# pioneer_2-bluepill_eletronic_wrapper.net
KiCad netlist of a schematic drawn in Altium Designer
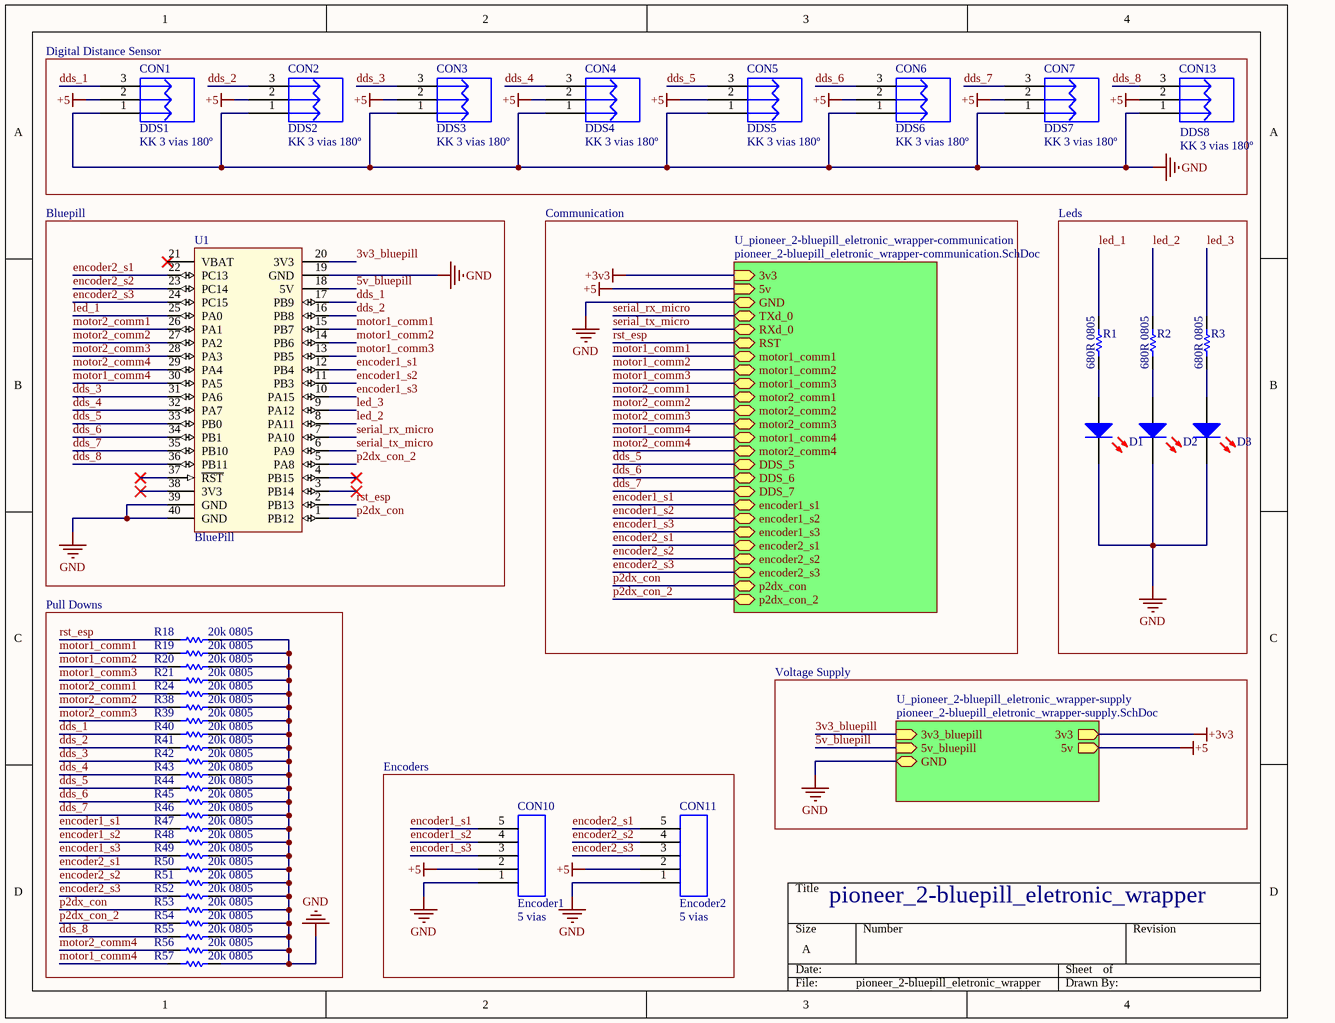
[diagram p0: pioneer_2-bluepill_eletronic_wrapper.SchDoc]

(export (version "E")
  (design (tool "Eeschema 10.0.6"))
  (components
    (comp (ref "CON1")
      (value "DDS1")
      (footprint "KK_3vias_180º")
      (description "Conector KK 2.54mm 3 vias")
      (fields (field (name "VALOR") "KK 3 vias 180º"))
      (libsource (lib "pioneer_2-bluepill_eletronic_wrapper") (part "KK_2.54_3vias"))
    )
    (comp (ref "CON2")
      (value "DDS2")
      (footprint "KK_3vias_180º")
      (description "Conector KK 2.54mm 3 vias")
      (fields (field (name "VALOR") "KK 3 vias 180º"))
      (libsource (lib "pioneer_2-bluepill_eletronic_wrapper") (part "KK_2.54_3vias"))
    )
    (comp (ref "CON3")
      (value "DDS3")
      (footprint "KK_3vias_180º")
      (description "Conector KK 2.54mm 3 vias")
      (fields (field (name "VALOR") "KK 3 vias 180º"))
      (libsource (lib "pioneer_2-bluepill_eletronic_wrapper") (part "KK_2.54_3vias"))
    )
    (comp (ref "CON4")
      (value "DDS4")
      (footprint "KK_3vias_180º")
      (description "Conector KK 2.54mm 3 vias")
      (fields (field (name "VALOR") "KK 3 vias 180º"))
      (libsource (lib "pioneer_2-bluepill_eletronic_wrapper") (part "KK_2.54_3vias"))
    )
    (comp (ref "CON5")
      (value "DDS5")
      (footprint "KK_3vias_180º")
      (description "Conector KK 2.54mm 3 vias")
      (fields (field (name "VALOR") "KK 3 vias 180º"))
      (libsource (lib "pioneer_2-bluepill_eletronic_wrapper") (part "KK_2.54_3vias"))
    )
    (comp (ref "CON6")
      (value "DDS6")
      (footprint "KK_3vias_180º")
      (description "Conector KK 2.54mm 3 vias")
      (fields (field (name "VALOR") "KK 3 vias 180º"))
      (libsource (lib "pioneer_2-bluepill_eletronic_wrapper") (part "KK_2.54_3vias"))
    )
    (comp (ref "CON7")
      (value "DDS7")
      (footprint "KK_3vias_180º")
      (description "Conector KK 2.54mm 3 vias")
      (fields (field (name "VALOR") "KK 3 vias 180º"))
      (libsource (lib "pioneer_2-bluepill_eletronic_wrapper") (part "KK_2.54_3vias"))
    )
    (comp (ref "CON10")
      (value "Encoder1")
      (footprint "5vias")
      (description "holes 2.54mm 5 vias")
      (fields (field (name "VALOR") "5 vias"))
      (libsource (lib "pioneer_2-bluepill_eletronic_wrapper") (part "2.54_5vias"))
    )
    (comp (ref "CON11")
      (value "Encoder2")
      (footprint "5vias")
      (description "holes 2.54mm 5 vias")
      (fields (field (name "VALOR") "5 vias"))
      (libsource (lib "pioneer_2-bluepill_eletronic_wrapper") (part "2.54_5vias"))
    )
    (comp (ref "CON13")
      (value "DDS8")
      (footprint "KK_3vias_180º")
      (description "Conector KK 2.54mm 3 vias")
      (fields (field (name "VALOR") "KK 3 vias 180º"))
      (libsource (lib "pioneer_2-bluepill_eletronic_wrapper") (part "KK_2.54_3vias"))
    )
    (comp (ref "D1")
      (value "LED 3MM RED")
      (footprint "LED RED")
      (fields (field (name "MANUFACTURER") "Paralight") (field (name "MANUFACTURER PART NUMBER") "IMP585"))
      (libsource (lib "pioneer_2-bluepill_eletronic_wrapper") (part "LED 3MM RED"))
    )
    (comp (ref "D2")
      (value "LED 3MM RED")
      (footprint "LED RED")
      (fields (field (name "MANUFACTURER") "Paralight") (field (name "MANUFACTURER PART NUMBER") "IMP585"))
      (libsource (lib "pioneer_2-bluepill_eletronic_wrapper") (part "LED 3MM RED"))
    )
    (comp (ref "D3")
      (value "LED 3MM RED")
      (footprint "LED RED")
      (fields (field (name "MANUFACTURER") "Paralight") (field (name "MANUFACTURER PART NUMBER") "IMP585"))
      (libsource (lib "pioneer_2-bluepill_eletronic_wrapper") (part "LED 3MM RED"))
    )
    (comp (ref "R1")
      (value "680R 0805")
      (footprint "RESISTOR 0805")
      (description "0805")
      (fields
        (field (name "MANUFACTURER") "PANASONIC ELECTRONIC COMPONENTS")
        (field (name "MANUFACTURER PART NUMBER") "ERJ-3GEY0R00V")
      )
      (libsource (lib "pioneer_2-bluepill_eletronic_wrapper") (part "RES 0805 5%"))
    )
    (comp (ref "R2")
      (value "680R 0805")
      (footprint "RESISTOR 0805")
      (description "0805")
      (fields
        (field (name "MANUFACTURER") "PANASONIC ELECTRONIC COMPONENTS")
        (field (name "MANUFACTURER PART NUMBER") "ERJ-3GEY0R00V")
      )
      (libsource (lib "pioneer_2-bluepill_eletronic_wrapper") (part "RES 0805 5%"))
    )
    (comp (ref "R3")
      (value "680R 0805")
      (footprint "RESISTOR 0805")
      (description "0805")
      (fields
        (field (name "MANUFACTURER") "PANASONIC ELECTRONIC COMPONENTS")
        (field (name "MANUFACTURER PART NUMBER") "ERJ-3GEY0R00V")
      )
      (libsource (lib "pioneer_2-bluepill_eletronic_wrapper") (part "RES 0805 5%"))
    )
    (comp (ref "R18")
      (value "20k 0805")
      (footprint "RESISTOR 0805")
      (description "0805")
      (fields
        (field (name "MANUFACTURER") "PANASONIC ELECTRONIC COMPONENTS")
        (field (name "MANUFACTURER PART NUMBER") "ERJ-3GEY0R00V")
      )
      (libsource (lib "pioneer_2-bluepill_eletronic_wrapper") (part "RES 0805 5%"))
    )
    (comp (ref "R19")
      (value "20k 0805")
      (footprint "RESISTOR 0805")
      (description "0805")
      (fields
        (field (name "MANUFACTURER") "PANASONIC ELECTRONIC COMPONENTS")
        (field (name "MANUFACTURER PART NUMBER") "ERJ-3GEY0R00V")
      )
      (libsource (lib "pioneer_2-bluepill_eletronic_wrapper") (part "RES 0805 5%"))
    )
    (comp (ref "R20")
      (value "20k 0805")
      (footprint "RESISTOR 0805")
      (description "0805")
      (fields
        (field (name "MANUFACTURER") "PANASONIC ELECTRONIC COMPONENTS")
        (field (name "MANUFACTURER PART NUMBER") "ERJ-3GEY0R00V")
      )
      (libsource (lib "pioneer_2-bluepill_eletronic_wrapper") (part "RES 0805 5%"))
    )
    (comp (ref "R21")
      (value "20k 0805")
      (footprint "RESISTOR 0805")
      (description "0805")
      (fields
        (field (name "MANUFACTURER") "PANASONIC ELECTRONIC COMPONENTS")
        (field (name "MANUFACTURER PART NUMBER") "ERJ-3GEY0R00V")
      )
      (libsource (lib "pioneer_2-bluepill_eletronic_wrapper") (part "RES 0805 5%"))
    )
    (comp (ref "R24")
      (value "20k 0805")
      (footprint "RESISTOR 0805")
      (description "0805")
      (fields
        (field (name "MANUFACTURER") "PANASONIC ELECTRONIC COMPONENTS")
        (field (name "MANUFACTURER PART NUMBER") "ERJ-3GEY0R00V")
      )
      (libsource (lib "pioneer_2-bluepill_eletronic_wrapper") (part "RES 0805 5%"))
    )
    (comp (ref "R38")
      (value "20k 0805")
      (footprint "RESISTOR 0805")
      (description "0805")
      (fields
        (field (name "MANUFACTURER") "PANASONIC ELECTRONIC COMPONENTS")
        (field (name "MANUFACTURER PART NUMBER") "ERJ-3GEY0R00V")
      )
      (libsource (lib "pioneer_2-bluepill_eletronic_wrapper") (part "RES 0805 5%"))
    )
    (comp (ref "R39")
      (value "20k 0805")
      (footprint "RESISTOR 0805")
      (description "0805")
      (fields
        (field (name "MANUFACTURER") "PANASONIC ELECTRONIC COMPONENTS")
        (field (name "MANUFACTURER PART NUMBER") "ERJ-3GEY0R00V")
      )
      (libsource (lib "pioneer_2-bluepill_eletronic_wrapper") (part "RES 0805 5%"))
    )
    (comp (ref "R40")
      (value "20k 0805")
      (footprint "RESISTOR 0805")
      (description "0805")
      (fields
        (field (name "MANUFACTURER") "PANASONIC ELECTRONIC COMPONENTS")
        (field (name "MANUFACTURER PART NUMBER") "ERJ-3GEY0R00V")
      )
      (libsource (lib "pioneer_2-bluepill_eletronic_wrapper") (part "RES 0805 5%"))
    )
    (comp (ref "R41")
      (value "20k 0805")
      (footprint "RESISTOR 0805")
      (description "0805")
      (fields
        (field (name "MANUFACTURER") "PANASONIC ELECTRONIC COMPONENTS")
        (field (name "MANUFACTURER PART NUMBER") "ERJ-3GEY0R00V")
      )
      (libsource (lib "pioneer_2-bluepill_eletronic_wrapper") (part "RES 0805 5%"))
    )
    (comp (ref "R42")
      (value "20k 0805")
      (footprint "RESISTOR 0805")
      (description "0805")
      (fields
        (field (name "MANUFACTURER") "PANASONIC ELECTRONIC COMPONENTS")
        (field (name "MANUFACTURER PART NUMBER") "ERJ-3GEY0R00V")
      )
      (libsource (lib "pioneer_2-bluepill_eletronic_wrapper") (part "RES 0805 5%"))
    )
    (comp (ref "R43")
      (value "20k 0805")
      (footprint "RESISTOR 0805")
      (description "0805")
      (fields
        (field (name "MANUFACTURER") "PANASONIC ELECTRONIC COMPONENTS")
        (field (name "MANUFACTURER PART NUMBER") "ERJ-3GEY0R00V")
      )
      (libsource (lib "pioneer_2-bluepill_eletronic_wrapper") (part "RES 0805 5%"))
    )
    (comp (ref "R44")
      (value "20k 0805")
      (footprint "RESISTOR 0805")
      (description "0805")
      (fields
        (field (name "MANUFACTURER") "PANASONIC ELECTRONIC COMPONENTS")
        (field (name "MANUFACTURER PART NUMBER") "ERJ-3GEY0R00V")
      )
      (libsource (lib "pioneer_2-bluepill_eletronic_wrapper") (part "RES 0805 5%"))
    )
    (comp (ref "R45")
      (value "20k 0805")
      (footprint "RESISTOR 0805")
      (description "0805")
      (fields
        (field (name "MANUFACTURER") "PANASONIC ELECTRONIC COMPONENTS")
        (field (name "MANUFACTURER PART NUMBER") "ERJ-3GEY0R00V")
      )
      (libsource (lib "pioneer_2-bluepill_eletronic_wrapper") (part "RES 0805 5%"))
    )
    (comp (ref "R46")
      (value "20k 0805")
      (footprint "RESISTOR 0805")
      (description "0805")
      (fields
        (field (name "MANUFACTURER") "PANASONIC ELECTRONIC COMPONENTS")
        (field (name "MANUFACTURER PART NUMBER") "ERJ-3GEY0R00V")
      )
      (libsource (lib "pioneer_2-bluepill_eletronic_wrapper") (part "RES 0805 5%"))
    )
    (comp (ref "R47")
      (value "20k 0805")
      (footprint "RESISTOR 0805")
      (description "0805")
      (fields
        (field (name "MANUFACTURER") "PANASONIC ELECTRONIC COMPONENTS")
        (field (name "MANUFACTURER PART NUMBER") "ERJ-3GEY0R00V")
      )
      (libsource (lib "pioneer_2-bluepill_eletronic_wrapper") (part "RES 0805 5%"))
    )
    (comp (ref "R48")
      (value "20k 0805")
      (footprint "RESISTOR 0805")
      (description "0805")
      (fields
        (field (name "MANUFACTURER") "PANASONIC ELECTRONIC COMPONENTS")
        (field (name "MANUFACTURER PART NUMBER") "ERJ-3GEY0R00V")
      )
      (libsource (lib "pioneer_2-bluepill_eletronic_wrapper") (part "RES 0805 5%"))
    )
    (comp (ref "R49")
      (value "20k 0805")
      (footprint "RESISTOR 0805")
      (description "0805")
      (fields
        (field (name "MANUFACTURER") "PANASONIC ELECTRONIC COMPONENTS")
        (field (name "MANUFACTURER PART NUMBER") "ERJ-3GEY0R00V")
      )
      (libsource (lib "pioneer_2-bluepill_eletronic_wrapper") (part "RES 0805 5%"))
    )
    (comp (ref "R50")
      (value "20k 0805")
      (footprint "RESISTOR 0805")
      (description "0805")
      (fields
        (field (name "MANUFACTURER") "PANASONIC ELECTRONIC COMPONENTS")
        (field (name "MANUFACTURER PART NUMBER") "ERJ-3GEY0R00V")
      )
      (libsource (lib "pioneer_2-bluepill_eletronic_wrapper") (part "RES 0805 5%"))
    )
    (comp (ref "R51")
      (value "20k 0805")
      (footprint "RESISTOR 0805")
      (description "0805")
      (fields
        (field (name "MANUFACTURER") "PANASONIC ELECTRONIC COMPONENTS")
        (field (name "MANUFACTURER PART NUMBER") "ERJ-3GEY0R00V")
      )
      (libsource (lib "pioneer_2-bluepill_eletronic_wrapper") (part "RES 0805 5%"))
    )
    (comp (ref "R52")
      (value "20k 0805")
      (footprint "RESISTOR 0805")
      (description "0805")
      (fields
        (field (name "MANUFACTURER") "PANASONIC ELECTRONIC COMPONENTS")
        (field (name "MANUFACTURER PART NUMBER") "ERJ-3GEY0R00V")
      )
      (libsource (lib "pioneer_2-bluepill_eletronic_wrapper") (part "RES 0805 5%"))
    )
    (comp (ref "R53")
      (value "20k 0805")
      (footprint "RESISTOR 0805")
      (description "0805")
      (fields
        (field (name "MANUFACTURER") "PANASONIC ELECTRONIC COMPONENTS")
        (field (name "MANUFACTURER PART NUMBER") "ERJ-3GEY0R00V")
      )
      (libsource (lib "pioneer_2-bluepill_eletronic_wrapper") (part "RES 0805 5%"))
    )
    (comp (ref "R54")
      (value "20k 0805")
      (footprint "RESISTOR 0805")
      (description "0805")
      (fields
        (field (name "MANUFACTURER") "PANASONIC ELECTRONIC COMPONENTS")
        (field (name "MANUFACTURER PART NUMBER") "ERJ-3GEY0R00V")
      )
      (libsource (lib "pioneer_2-bluepill_eletronic_wrapper") (part "RES 0805 5%"))
    )
    (comp (ref "R55")
      (value "20k 0805")
      (footprint "RESISTOR 0805")
      (description "0805")
      (fields
        (field (name "MANUFACTURER") "PANASONIC ELECTRONIC COMPONENTS")
        (field (name "MANUFACTURER PART NUMBER") "ERJ-3GEY0R00V")
      )
      (libsource (lib "pioneer_2-bluepill_eletronic_wrapper") (part "RES 0805 5%"))
    )
    (comp (ref "R56")
      (value "20k 0805")
      (footprint "RESISTOR 0805")
      (description "0805")
      (fields
        (field (name "MANUFACTURER") "PANASONIC ELECTRONIC COMPONENTS")
        (field (name "MANUFACTURER PART NUMBER") "ERJ-3GEY0R00V")
      )
      (libsource (lib "pioneer_2-bluepill_eletronic_wrapper") (part "RES 0805 5%"))
    )
    (comp (ref "R57")
      (value "20k 0805")
      (footprint "RESISTOR 0805")
      (description "0805")
      (fields
        (field (name "MANUFACTURER") "PANASONIC ELECTRONIC COMPONENTS")
        (field (name "MANUFACTURER PART NUMBER") "ERJ-3GEY0R00V")
      )
      (libsource (lib "pioneer_2-bluepill_eletronic_wrapper") (part "RES 0805 5%"))
    )
    (comp (ref "U1")
      (value "BluePill")
      (footprint "BluePill")
      (description "BluePill - STMDuino (STM32F103)")
      (fields (field (name "SOURCE") "uControlador.SchLib"))
      (libsource (lib "pioneer_2-bluepill_eletronic_wrapper") (part "CMP-010-000000-1"))
    )
  )
  (nets
    (net (code "2") (name "+5") (class "Default")
      (node (ref "CON1") (pin "2") (pintype "passive"))
      (node (ref "CON10") (pin "2") (pintype "passive"))
      (node (ref "CON11") (pin "2") (pintype "passive"))
      (node (ref "CON13") (pin "2") (pintype "passive"))
      (node (ref "CON2") (pin "2") (pintype "passive"))
      (node (ref "CON3") (pin "2") (pintype "passive"))
      (node (ref "CON4") (pin "2") (pintype "passive"))
      (node (ref "CON5") (pin "2") (pintype "passive"))
      (node (ref "CON6") (pin "2") (pintype "passive"))
      (node (ref "CON7") (pin "2") (pintype "passive"))
    )
    (net (code "3") (name "/3v3_bluepill") (class "Default")
      (node (ref "U1") (pin "20") (pinfunction "3V3_20") (pintype "passive"))
    )
    (net (code "4") (name "/5v_bluepill") (class "Default")
      (node (ref "U1") (pin "18") (pinfunction "5V_18") (pintype "power_in"))
    )
    (net (code "5") (name "/dds_1") (class "Default")
      (node (ref "CON1") (pin "3") (pintype "passive"))
      (node (ref "R40") (pin "1") (pinfunction "1_1") (pintype "passive"))
      (node (ref "U1") (pin "17") (pinfunction "PB9_17") (pintype "bidirectional"))
    )
    (net (code "6") (name "/dds_2") (class "Default")
      (node (ref "CON2") (pin "3") (pintype "passive"))
      (node (ref "R41") (pin "1") (pinfunction "1_1") (pintype "passive"))
      (node (ref "U1") (pin "16") (pinfunction "PB8_16") (pintype "bidirectional"))
    )
    (net (code "7") (name "/dds_3") (class "Default")
      (node (ref "CON3") (pin "3") (pintype "passive"))
      (node (ref "R42") (pin "1") (pinfunction "1_1") (pintype "passive"))
      (node (ref "U1") (pin "31") (pinfunction "PA6_31") (pintype "bidirectional"))
    )
    (net (code "8") (name "/dds_4") (class "Default")
      (node (ref "CON4") (pin "3") (pintype "passive"))
      (node (ref "R43") (pin "1") (pinfunction "1_1") (pintype "passive"))
      (node (ref "U1") (pin "32") (pinfunction "PA7_32") (pintype "bidirectional"))
    )
    (net (code "9") (name "/dds_5") (class "Default")
      (node (ref "CON5") (pin "3") (pintype "passive"))
      (node (ref "R44") (pin "1") (pinfunction "1_1") (pintype "passive"))
      (node (ref "U1") (pin "33") (pinfunction "PB0_33") (pintype "bidirectional"))
    )
    (net (code "10") (name "/dds_6") (class "Default")
      (node (ref "CON6") (pin "3") (pintype "passive"))
      (node (ref "R45") (pin "1") (pinfunction "1_1") (pintype "passive"))
      (node (ref "U1") (pin "34") (pinfunction "PB1_34") (pintype "bidirectional"))
    )
    (net (code "11") (name "/dds_7") (class "Default")
      (node (ref "CON7") (pin "3") (pintype "passive"))
      (node (ref "R46") (pin "1") (pinfunction "1_1") (pintype "passive"))
      (node (ref "U1") (pin "35") (pinfunction "PB10_35") (pintype "bidirectional"))
    )
    (net (code "12") (name "/dds_8") (class "Default")
      (node (ref "CON13") (pin "3") (pintype "passive"))
      (node (ref "R55") (pin "1") (pinfunction "1_1") (pintype "passive"))
      (node (ref "U1") (pin "36") (pinfunction "PB11_36") (pintype "bidirectional"))
    )
    (net (code "13") (name "/encoder1_s1") (class "Default")
      (node (ref "CON10") (pin "5") (pintype "passive"))
      (node (ref "R47") (pin "1") (pinfunction "1_1") (pintype "passive"))
      (node (ref "U1") (pin "12") (pinfunction "PB4_12") (pintype "bidirectional"))
    )
    (net (code "14") (name "/encoder1_s2") (class "Default")
      (node (ref "CON10") (pin "4") (pintype "passive"))
      (node (ref "R48") (pin "1") (pinfunction "1_1") (pintype "passive"))
      (node (ref "U1") (pin "11") (pinfunction "PB3_11") (pintype "bidirectional"))
    )
    (net (code "15") (name "/encoder1_s3") (class "Default")
      (node (ref "CON10") (pin "3") (pintype "passive"))
      (node (ref "R49") (pin "1") (pinfunction "1_1") (pintype "passive"))
      (node (ref "U1") (pin "10") (pinfunction "PA15_10") (pintype "bidirectional"))
    )
    (net (code "16") (name "/encoder2_s1") (class "Default")
      (node (ref "CON11") (pin "5") (pintype "passive"))
      (node (ref "R50") (pin "1") (pinfunction "1_1") (pintype "passive"))
      (node (ref "U1") (pin "22") (pinfunction "PC13_22") (pintype "bidirectional"))
    )
    (net (code "17") (name "/encoder2_s2") (class "Default")
      (node (ref "CON11") (pin "4") (pintype "passive"))
      (node (ref "R51") (pin "1") (pinfunction "1_1") (pintype "passive"))
      (node (ref "U1") (pin "23") (pinfunction "PC14_23") (pintype "bidirectional"))
    )
    (net (code "18") (name "/encoder2_s3") (class "Default")
      (node (ref "CON11") (pin "3") (pintype "passive"))
      (node (ref "R52") (pin "1") (pinfunction "1_1") (pintype "passive"))
      (node (ref "U1") (pin "24") (pinfunction "PC15_24") (pintype "bidirectional"))
    )
    (net (code "19") (name "/led_1") (class "Default")
      (node (ref "R1") (pin "2") (pinfunction "2_2") (pintype "passive"))
      (node (ref "U1") (pin "25") (pinfunction "PA0_25") (pintype "bidirectional"))
    )
    (net (code "20") (name "/led_2") (class "Default")
      (node (ref "R2") (pin "2") (pinfunction "2_2") (pintype "passive"))
      (node (ref "U1") (pin "8") (pinfunction "PA11_8") (pintype "bidirectional"))
    )
    (net (code "21") (name "/led_3") (class "Default")
      (node (ref "R3") (pin "2") (pinfunction "2_2") (pintype "passive"))
      (node (ref "U1") (pin "9") (pinfunction "PA12_9") (pintype "bidirectional"))
    )
    (net (code "22") (name "/motor1_comm1") (class "Default")
      (node (ref "R19") (pin "1") (pinfunction "1_1") (pintype "passive"))
      (node (ref "U1") (pin "15") (pinfunction "PB7_15") (pintype "bidirectional"))
    )
    (net (code "23") (name "/motor1_comm2") (class "Default")
      (node (ref "R20") (pin "1") (pinfunction "1_1") (pintype "passive"))
      (node (ref "U1") (pin "14") (pinfunction "PB6_14") (pintype "bidirectional"))
    )
    (net (code "24") (name "/motor1_comm3") (class "Default")
      (node (ref "R21") (pin "1") (pinfunction "1_1") (pintype "passive"))
      (node (ref "U1") (pin "13") (pinfunction "PB5_13") (pintype "bidirectional"))
    )
    (net (code "25") (name "/motor1_comm4") (class "Default")
      (node (ref "R57") (pin "1") (pinfunction "1_1") (pintype "passive"))
      (node (ref "U1") (pin "30") (pinfunction "PA5_30") (pintype "bidirectional"))
    )
    (net (code "26") (name "/motor2_comm1") (class "Default")
      (node (ref "R24") (pin "1") (pinfunction "1_1") (pintype "passive"))
      (node (ref "U1") (pin "26") (pinfunction "PA1_26") (pintype "bidirectional"))
    )
    (net (code "27") (name "/motor2_comm2") (class "Default")
      (node (ref "R38") (pin "1") (pinfunction "1_1") (pintype "passive"))
      (node (ref "U1") (pin "27") (pinfunction "PA2_27") (pintype "bidirectional"))
    )
    (net (code "28") (name "/motor2_comm3") (class "Default")
      (node (ref "R39") (pin "1") (pinfunction "1_1") (pintype "passive"))
      (node (ref "U1") (pin "28") (pinfunction "PA3_28") (pintype "bidirectional"))
    )
    (net (code "29") (name "/motor2_comm4") (class "Default")
      (node (ref "R56") (pin "1") (pinfunction "1_1") (pintype "passive"))
      (node (ref "U1") (pin "29") (pinfunction "PA4_29") (pintype "bidirectional"))
    )
    (net (code "30") (name "/p2dx_con") (class "Default")
      (node (ref "R53") (pin "1") (pinfunction "1_1") (pintype "passive"))
      (node (ref "U1") (pin "1") (pinfunction "PB12_1") (pintype "bidirectional"))
    )
    (net (code "31") (name "/p2dx_con_2") (class "Default")
      (node (ref "R54") (pin "1") (pinfunction "1_1") (pintype "passive"))
      (node (ref "U1") (pin "5") (pinfunction "PA8_5") (pintype "bidirectional"))
    )
    (net (code "32") (name "/rst_esp") (class "Default")
      (node (ref "R18") (pin "1") (pinfunction "1_1") (pintype "passive"))
      (node (ref "U1") (pin "2") (pinfunction "PB13_2") (pintype "bidirectional"))
    )
    (net (code "33") (name "/serial_rx_micro") (class "Default")
      (node (ref "U1") (pin "7") (pinfunction "PA10_7") (pintype "bidirectional"))
    )
    (net (code "34") (name "/serial_tx_micro") (class "Default")
      (node (ref "U1") (pin "6") (pinfunction "PA9_6") (pintype "bidirectional"))
    )
    (net (code "35") (name "GND") (class "Default")
      (node (ref "CON1") (pin "1") (pintype "passive"))
      (node (ref "CON10") (pin "1") (pintype "passive"))
      (node (ref "CON11") (pin "1") (pintype "passive"))
      (node (ref "CON13") (pin "1") (pintype "passive"))
      (node (ref "CON2") (pin "1") (pintype "passive"))
      (node (ref "CON3") (pin "1") (pintype "passive"))
      (node (ref "CON4") (pin "1") (pintype "passive"))
      (node (ref "CON5") (pin "1") (pintype "passive"))
      (node (ref "CON6") (pin "1") (pintype "passive"))
      (node (ref "CON7") (pin "1") (pintype "passive"))
      (node (ref "D1") (pin "2") (pinfunction "K_2") (pintype "passive"))
      (node (ref "D2") (pin "2") (pinfunction "K_2") (pintype "passive"))
      (node (ref "D3") (pin "2") (pinfunction "K_2") (pintype "passive"))
      (node (ref "R18") (pin "2") (pinfunction "2_2") (pintype "passive"))
      (node (ref "R19") (pin "2") (pinfunction "2_2") (pintype "passive"))
      (node (ref "R20") (pin "2") (pinfunction "2_2") (pintype "passive"))
      (node (ref "R21") (pin "2") (pinfunction "2_2") (pintype "passive"))
      (node (ref "R24") (pin "2") (pinfunction "2_2") (pintype "passive"))
      (node (ref "R38") (pin "2") (pinfunction "2_2") (pintype "passive"))
      (node (ref "R39") (pin "2") (pinfunction "2_2") (pintype "passive"))
      (node (ref "R40") (pin "2") (pinfunction "2_2") (pintype "passive"))
      (node (ref "R41") (pin "2") (pinfunction "2_2") (pintype "passive"))
      (node (ref "R42") (pin "2") (pinfunction "2_2") (pintype "passive"))
      (node (ref "R43") (pin "2") (pinfunction "2_2") (pintype "passive"))
      (node (ref "R44") (pin "2") (pinfunction "2_2") (pintype "passive"))
      (node (ref "R45") (pin "2") (pinfunction "2_2") (pintype "passive"))
      (node (ref "R46") (pin "2") (pinfunction "2_2") (pintype "passive"))
      (node (ref "R47") (pin "2") (pinfunction "2_2") (pintype "passive"))
      (node (ref "R48") (pin "2") (pinfunction "2_2") (pintype "passive"))
      (node (ref "R49") (pin "2") (pinfunction "2_2") (pintype "passive"))
      (node (ref "R50") (pin "2") (pinfunction "2_2") (pintype "passive"))
      (node (ref "R51") (pin "2") (pinfunction "2_2") (pintype "passive"))
      (node (ref "R52") (pin "2") (pinfunction "2_2") (pintype "passive"))
      (node (ref "R53") (pin "2") (pinfunction "2_2") (pintype "passive"))
      (node (ref "R54") (pin "2") (pinfunction "2_2") (pintype "passive"))
      (node (ref "R55") (pin "2") (pinfunction "2_2") (pintype "passive"))
      (node (ref "R56") (pin "2") (pinfunction "2_2") (pintype "passive"))
      (node (ref "R57") (pin "2") (pinfunction "2_2") (pintype "passive"))
      (node (ref "U1") (pin "19") (pinfunction "GND_19") (pintype "passive"))
      (node (ref "U1") (pin "39") (pinfunction "GND_39") (pintype "passive"))
      (node (ref "U1") (pin "40") (pinfunction "GND_40") (pintype "passive"))
    )
    (net (code "36") (name "Net-(D1-A)") (class "Default")
      (node (ref "D1") (pin "1") (pinfunction "A_1") (pintype "passive"))
      (node (ref "R1") (pin "1") (pinfunction "1_1") (pintype "passive"))
    )
    (net (code "37") (name "Net-(D2-A)") (class "Default")
      (node (ref "D2") (pin "1") (pinfunction "A_1") (pintype "passive"))
      (node (ref "R2") (pin "1") (pinfunction "1_1") (pintype "passive"))
    )
    (net (code "38") (name "Net-(D3-A)") (class "Default")
      (node (ref "D3") (pin "1") (pinfunction "A_1") (pintype "passive"))
      (node (ref "R3") (pin "1") (pinfunction "1_1") (pintype "passive"))
    )
    (net (code "39") (name "unconnected-(U1-3V3-Pad38)") (class "Default")
      (node (ref "U1") (pin "38") (pinfunction "3V3_38") (pintype "power_in+no_connect"))
    )
    (net (code "40") (name "unconnected-(U1-PB14-Pad3)") (class "Default")
      (node (ref "U1") (pin "3") (pinfunction "PB14_3") (pintype "bidirectional+no_connect"))
    )
    (net (code "41") (name "unconnected-(U1-PB15-Pad4)") (class "Default")
      (node (ref "U1") (pin "4") (pinfunction "PB15_4") (pintype "bidirectional+no_connect"))
    )
    (net (code "42") (name "unconnected-(U1-VBAT-Pad21)") (class "Default")
      (node (ref "U1") (pin "21") (pinfunction "VBAT_21") (pintype "power_in+no_connect"))
    )
    (net (code "43") (name "unconnected-(U1-~{RST}-Pad37)") (class "Default")
      (node (ref "U1") (pin "37") (pinfunction "~{RST}_37") (pintype "input+no_connect"))
    )
  )
)
